# CH32F203K8T6-R0.net
KiCad netlist of a schematic drawn in Altium Designer
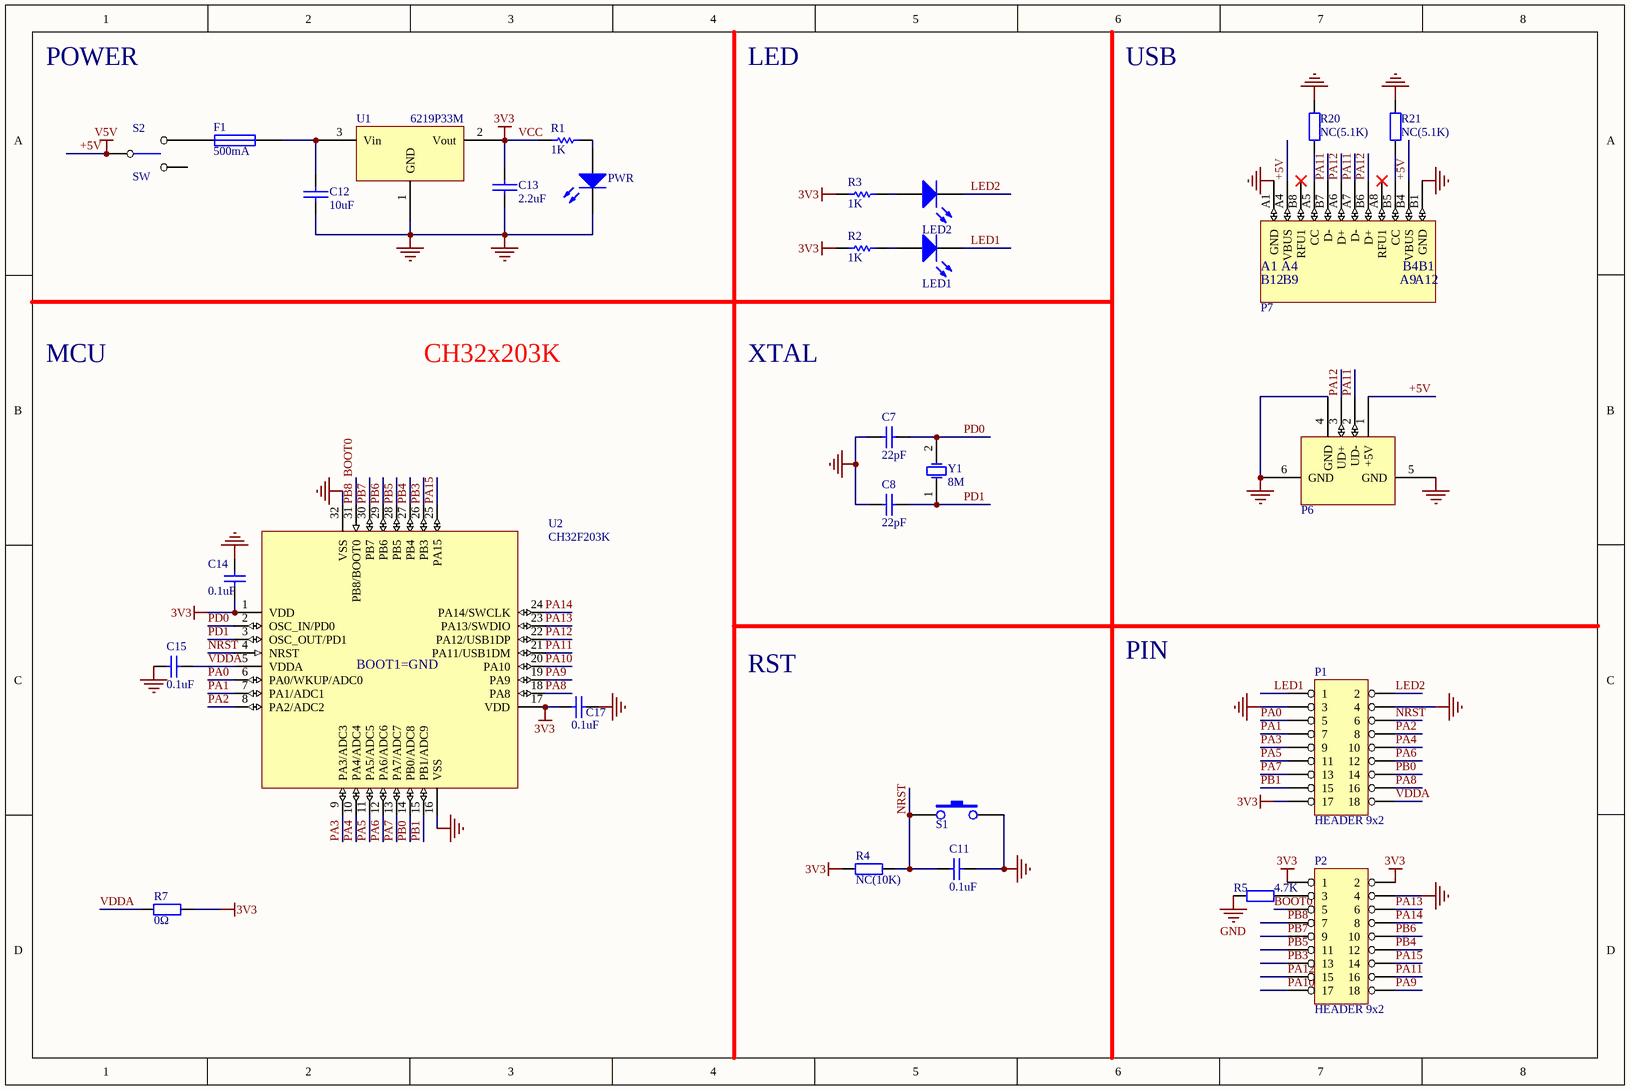
[diagram p0: CH32F203K8T6-R0.SchDoc]

(export (version "E")
  (design (tool "Eeschema 10.0.6"))
  (components
    (comp (ref "C7")
      (value "22pF")
      (footprint "0603_C")
      (description "Capacitor")
      (fields (field (name "PUBLISHER") "Altium Limited"))
      (libsource (lib "*") (part "Cap"))
    )
    (comp (ref "C8")
      (value "22pF")
      (footprint "0603_C")
      (description "Capacitor")
      (fields (field (name "PUBLISHER") "Altium Limited"))
      (libsource (lib "*") (part "Cap"))
    )
    (comp (ref "C11")
      (value "0.1uF")
      (footprint "0603_C")
      (description "Capacitor")
      (fields (field (name "PUBLISHER") "Altium Limited"))
      (libsource (lib "*") (part "Cap"))
    )
    (comp (ref "C12")
      (value "10uF")
      (footprint "3216_C")
      (description "Capacitor")
      (libsource (lib "wch_sch_others") (part "CAP"))
    )
    (comp (ref "C13")
      (value "2.2uF")
      (footprint "0603_C")
      (description "Capacitor")
      (libsource (lib "wch_sch_others") (part "CAP"))
    )
    (comp (ref "C14")
      (value "0.1uF")
      (footprint "0603_C")
      (description "Capacitor")
      (fields (field (name "PUBLISHER") "Altium Limited"))
      (libsource (lib "*") (part "Cap"))
    )
    (comp (ref "C15")
      (value "0.1uF")
      (footprint "0603_C")
      (description "Capacitor")
      (fields (field (name "PUBLISHER") "Altium Limited"))
      (libsource (lib "*") (part "Cap"))
    )
    (comp (ref "C17")
      (value "0.1uF")
      (footprint "0603_C")
      (description "Capacitor")
      (fields (field (name "PUBLISHER") "Altium Limited"))
      (libsource (lib "*") (part "Cap"))
    )
    (comp (ref "F1")
      (value "500mA")
      (footprint "0603")
      (description "Fuse")
      (libsource (lib "*") (part "FUSE1"))
    )
    (comp (ref "LED1")
      (value "LED1   blue")
      (footprint "0603+")
      (description "Typical INFRARED GaAs LED")
      (fields (field (name "PUBLISHER") "Altium Limited"))
      (libsource (lib "*") (part "LED0"))
    )
    (comp (ref "LED2")
      (value "LED2  blue")
      (footprint "0603+")
      (description "Typical INFRARED GaAs LED")
      (fields (field (name "PUBLISHER") "Altium Limited"))
      (libsource (lib "*") (part "LED0"))
    )
    (comp (ref "P1")
      (value "HEADER 9x2")
      (footprint "MYPCB:IDC18-2.54MM")
      (description "Header, 9-Pin, Dual row")
      (libsource (lib "wch_sch_others") (part "HEADER 9x2"))
    )
    (comp (ref "P2")
      (value "HEADER 9x2")
      (footprint "MYPCB:IDC18-2.54MM")
      (description "Header, 9-Pin, Dual row")
      (libsource (lib "wch_sch_others") (part "HEADER 9x2"))
    )
    (comp (ref "P6")
      (value "USB_A")
      (footprint "USBAF")
      (description "USB Port")
      (libsource (lib "*") (part "USB"))
    )
    (comp (ref "P7")
      (value "TYPE-C")
      (footprint "TYPE-C-Receptacle-2.0")
      (libsource (lib "*") (part "TYPE-C1"))
    )
    (comp (ref "PWR")
      (value "POWER  red")
      (footprint "0603+")
      (description "Typical INFRARED GaAs LED")
      (fields (field (name "PUBLISHER") "Altium Limited"))
      (libsource (lib "*") (part "LED0"))
    )
    (comp (ref "R1")
      (value "1K")
      (footprint "0603")
      (description "Semiconductor Resistor")
      (fields (field (name "PUBLISHER") "Altium Limited"))
      (libsource (lib "*") (part "Res Semi"))
    )
    (comp (ref "R2")
      (value "1K")
      (footprint "0603")
      (description "Semiconductor Resistor")
      (fields (field (name "PUBLISHER") "Altium Limited"))
      (libsource (lib "*") (part "Res Semi"))
    )
    (comp (ref "R3")
      (value "1K")
      (footprint "0603")
      (description "Semiconductor Resistor")
      (fields (field (name "PUBLISHER") "Altium Limited"))
      (libsource (lib "*") (part "Res Semi"))
    )
    (comp (ref "R4")
      (value "NC(10K)")
      (footprint "0603")
      (description "Resistor")
      (fields (field (name "PUBLISHER") "Altium Limited"))
      (libsource (lib "*") (part "Res2"))
    )
    (comp (ref "R5")
      (value "4.7K")
      (footprint "0603")
      (description "Resistor")
      (fields (field (name "PUBLISHER") "Altium Limited"))
      (libsource (lib "") (part "Res2_1"))
    )
    (comp (ref "R7")
      (value "0Ω")
      (footprint "0603")
      (description "Resistor")
      (fields (field (name "PUBLISHER") "Altium Limited"))
      (libsource (lib "*") (part "Res2"))
    )
    (comp (ref "R20")
      (value "NC(5.1K)")
      (footprint "0603")
      (description "Resistor")
      (libsource (lib "Miscellaneous Devices") (part "Res2"))
    )
    (comp (ref "R21")
      (value "NC(5.1K)")
      (footprint "0603")
      (description "Resistor")
      (libsource (lib "Miscellaneous Devices") (part "Res2"))
    )
    (comp (ref "S1") (value "RST") (footprint "SMD_6.1x3.65x2.5mm-KEY") (libsource (lib "*") (part "KEY")))
    (comp (ref "S2") (value "SW") (footprint "KEY2") (libsource (lib "*") (part "SW")))
    (comp (ref "U1")
      (value "6219P33M")
      (footprint "SOT-23")
      (libsource (lib "wch_sch_others") (part "6219P33M"))
    )
    (comp (ref "U2")
      (value "CH32F203K")
      (footprint "LQFP32")
      (description "ARM M3 LMD-MCU, 144MHz, USB FS, CAN")
      (libsource (lib "CHXXX") (part "CH32F203K"))
    )
    (comp (ref "Y1")
      (value "8M")
      (footprint "XT_AT49")
      (description "Crystal Oscillator")
      (fields (field (name "PUBLISHER") "Altium Limited"))
      (libsource (lib "*") (part "XTAL"))
    )
  )
  (nets
    (net (code "2") (name "/BOOT0") (class "Default")
      (node (ref "P2") (pin "5") (pinfunction "5_5") (pintype "passive"))
      (node (ref "P2") (pin "7") (pinfunction "7_7") (pintype "passive"))
      (node (ref "U2") (pin "31") (pinfunction "PB8/BOOT0_31") (pintype "input"))
    )
    (net (code "3") (name "/LED1") (class "Default")
      (node (ref "LED1") (pin "2") (pinfunction "K_2") (pintype "passive"))
      (node (ref "P1") (pin "1") (pinfunction "1_1") (pintype "passive"))
    )
    (net (code "4") (name "/LED2") (class "Default")
      (node (ref "LED2") (pin "2") (pinfunction "K_2") (pintype "passive"))
      (node (ref "P1") (pin "2") (pinfunction "2_2") (pintype "passive"))
    )
    (net (code "5") (name "/NRST") (class "Default")
      (node (ref "C11") (pin "2") (pinfunction "2_2") (pintype "passive"))
      (node (ref "P1") (pin "6") (pinfunction "6_6") (pintype "passive"))
      (node (ref "R4") (pin "1") (pinfunction "1_1") (pintype "passive"))
      (node (ref "S1") (pin "1") (pinfunction "1_1") (pintype "passive"))
      (node (ref "U2") (pin "4") (pinfunction "NRST_4") (pintype "input"))
    )
    (net (code "6") (name "/PA0") (class "Default")
      (node (ref "P1") (pin "5") (pinfunction "5_5") (pintype "passive"))
      (node (ref "U2") (pin "6") (pinfunction "PA0/WKUP/ADC0_6") (pintype "bidirectional"))
    )
    (net (code "7") (name "/PA1") (class "Default")
      (node (ref "P1") (pin "7") (pinfunction "7_7") (pintype "passive"))
      (node (ref "U2") (pin "7") (pinfunction "PA1/ADC1_7") (pintype "bidirectional"))
    )
    (net (code "8") (name "/PA2") (class "Default")
      (node (ref "P1") (pin "8") (pinfunction "8_8") (pintype "passive"))
      (node (ref "U2") (pin "8") (pinfunction "PA2/ADC2_8") (pintype "bidirectional"))
    )
    (net (code "9") (name "/PA3") (class "Default")
      (node (ref "P1") (pin "9") (pinfunction "9_9") (pintype "passive"))
      (node (ref "U2") (pin "9") (pinfunction "PA3/ADC3_9") (pintype "bidirectional"))
    )
    (net (code "10") (name "/PA4") (class "Default")
      (node (ref "P1") (pin "10") (pinfunction "10_10") (pintype "passive"))
      (node (ref "U2") (pin "10") (pinfunction "PA4/ADC4_10") (pintype "bidirectional"))
    )
    (net (code "11") (name "/PA5") (class "Default")
      (node (ref "P1") (pin "11") (pinfunction "11_11") (pintype "passive"))
      (node (ref "U2") (pin "11") (pinfunction "PA5/ADC5_11") (pintype "bidirectional"))
    )
    (net (code "12") (name "/PA6") (class "Default")
      (node (ref "P1") (pin "12") (pinfunction "12_12") (pintype "passive"))
      (node (ref "U2") (pin "12") (pinfunction "PA6/ADC6_12") (pintype "bidirectional"))
    )
    (net (code "13") (name "/PA7") (class "Default")
      (node (ref "P1") (pin "13") (pinfunction "13_13") (pintype "passive"))
      (node (ref "U2") (pin "13") (pinfunction "PA7/ADC7_13") (pintype "bidirectional"))
    )
    (net (code "14") (name "/PA8") (class "Default")
      (node (ref "P1") (pin "16") (pinfunction "16_16") (pintype "passive"))
      (node (ref "U2") (pin "18") (pinfunction "PA8_18") (pintype "bidirectional"))
    )
    (net (code "15") (name "/PA9") (class "Default")
      (node (ref "P2") (pin "18") (pinfunction "18_18") (pintype "passive"))
      (node (ref "U2") (pin "19") (pinfunction "PA9_19") (pintype "bidirectional"))
    )
    (net (code "16") (name "/PA10") (class "Default")
      (node (ref "P2") (pin "17") (pinfunction "17_17") (pintype "passive"))
      (node (ref "U2") (pin "20") (pinfunction "PA10_20") (pintype "bidirectional"))
    )
    (net (code "17") (name "/PA11") (class "Default")
      (node (ref "P2") (pin "16") (pinfunction "16_16") (pintype "passive"))
      (node (ref "P6") (pin "2") (pinfunction "UD-_2") (pintype "bidirectional"))
      (node (ref "P7") (pin "A7") (pinfunction "D-_A7") (pintype "bidirectional"))
      (node (ref "P7") (pin "B7") (pinfunction "D-_B7") (pintype "bidirectional"))
      (node (ref "U2") (pin "21") (pinfunction "PA11/USB1DM_21") (pintype "bidirectional"))
    )
    (net (code "18") (name "/PA12") (class "Default")
      (node (ref "P2") (pin "15") (pinfunction "15_15") (pintype "passive"))
      (node (ref "P6") (pin "3") (pinfunction "UD+_3") (pintype "bidirectional"))
      (node (ref "P7") (pin "A6") (pinfunction "D+_A6") (pintype "bidirectional"))
      (node (ref "P7") (pin "B6") (pinfunction "D+_B6") (pintype "bidirectional"))
      (node (ref "U2") (pin "22") (pinfunction "PA12/USB1DP_22") (pintype "bidirectional"))
    )
    (net (code "19") (name "/PA13") (class "Default")
      (node (ref "P2") (pin "6") (pinfunction "6_6") (pintype "passive"))
      (node (ref "U2") (pin "23") (pinfunction "PA13/SWDIO_23") (pintype "bidirectional"))
    )
    (net (code "20") (name "/PA14") (class "Default")
      (node (ref "P2") (pin "8") (pinfunction "8_8") (pintype "passive"))
      (node (ref "U2") (pin "24") (pinfunction "PA14/SWCLK_24") (pintype "bidirectional"))
    )
    (net (code "21") (name "/PA15") (class "Default")
      (node (ref "P2") (pin "14") (pinfunction "14_14") (pintype "passive"))
      (node (ref "U2") (pin "25") (pinfunction "PA15_25") (pintype "bidirectional"))
    )
    (net (code "22") (name "/PB0") (class "Default")
      (node (ref "P1") (pin "14") (pinfunction "14_14") (pintype "passive"))
      (node (ref "U2") (pin "14") (pinfunction "PB0/ADC8_14") (pintype "bidirectional"))
    )
    (net (code "23") (name "/PB1") (class "Default")
      (node (ref "P1") (pin "15") (pinfunction "15_15") (pintype "passive"))
      (node (ref "U2") (pin "15") (pinfunction "PB1/ADC9_15") (pintype "bidirectional"))
    )
    (net (code "24") (name "/PB3") (class "Default")
      (node (ref "P2") (pin "13") (pinfunction "13_13") (pintype "passive"))
      (node (ref "U2") (pin "26") (pinfunction "PB3_26") (pintype "bidirectional"))
    )
    (net (code "25") (name "/PB4") (class "Default")
      (node (ref "P2") (pin "12") (pinfunction "12_12") (pintype "passive"))
      (node (ref "U2") (pin "27") (pinfunction "PB4_27") (pintype "bidirectional"))
    )
    (net (code "26") (name "/PB5") (class "Default")
      (node (ref "P2") (pin "11") (pinfunction "11_11") (pintype "passive"))
      (node (ref "U2") (pin "28") (pinfunction "PB5_28") (pintype "bidirectional"))
    )
    (net (code "27") (name "/PB6") (class "Default")
      (node (ref "P2") (pin "10") (pinfunction "10_10") (pintype "passive"))
      (node (ref "U2") (pin "29") (pinfunction "PB6_29") (pintype "bidirectional"))
    )
    (net (code "28") (name "/PB7") (class "Default")
      (node (ref "P2") (pin "9") (pinfunction "9_9") (pintype "passive"))
      (node (ref "U2") (pin "30") (pinfunction "PB7_30") (pintype "bidirectional"))
    )
    (net (code "29") (name "/PD0") (class "Default")
      (node (ref "C7") (pin "2") (pinfunction "2_2") (pintype "passive"))
      (node (ref "U2") (pin "2") (pinfunction "OSC_IN/PD0_2") (pintype "bidirectional"))
      (node (ref "Y1") (pin "2") (pinfunction "OSC2_2") (pintype "passive"))
    )
    (net (code "30") (name "/PD1") (class "Default")
      (node (ref "C8") (pin "2") (pinfunction "2_2") (pintype "passive"))
      (node (ref "U2") (pin "3") (pinfunction "OSC_OUT/PD1_3") (pintype "bidirectional"))
      (node (ref "Y1") (pin "1") (pinfunction "OSC1_1") (pintype "passive"))
    )
    (net (code "31") (name "/VDDA") (class "Default")
      (node (ref "C15") (pin "1") (pinfunction "1_1") (pintype "passive"))
      (node (ref "P1") (pin "18") (pinfunction "18_18") (pintype "passive"))
      (node (ref "R7") (pin "2") (pinfunction "2_2") (pintype "passive"))
      (node (ref "U2") (pin "5") (pinfunction "VDDA_5") (pintype "power_in"))
    )
    (net (code "32") (name "3V3") (class "Default")
      (node (ref "C13") (pin "2") (pinfunction "2_2") (pintype "passive"))
      (node (ref "C14") (pin "2") (pinfunction "2_2") (pintype "passive"))
      (node (ref "C17") (pin "1") (pinfunction "1_1") (pintype "passive"))
      (node (ref "P1") (pin "17") (pinfunction "17_17") (pintype "passive"))
      (node (ref "P2") (pin "1") (pinfunction "1_1") (pintype "passive"))
      (node (ref "P2") (pin "2") (pinfunction "2_2") (pintype "passive"))
      (node (ref "R1") (pin "2") (pinfunction "2_2") (pintype "passive"))
      (node (ref "R2") (pin "1") (pinfunction "1_1") (pintype "passive"))
      (node (ref "R3") (pin "1") (pinfunction "1_1") (pintype "passive"))
      (node (ref "R4") (pin "2") (pinfunction "2_2") (pintype "passive"))
      (node (ref "R7") (pin "1") (pinfunction "1_1") (pintype "passive"))
      (node (ref "U1") (pin "2") (pinfunction "Vout_2") (pintype "passive"))
      (node (ref "U2") (pin "1") (pinfunction "VDD_1") (pintype "power_in"))
      (node (ref "U2") (pin "17") (pinfunction "VDD_17") (pintype "power_in"))
    )
    (net (code "33") (name "GND") (class "Default")
      (node (ref "C11") (pin "1") (pinfunction "1_1") (pintype "passive"))
      (node (ref "C12") (pin "2") (pinfunction "2_2") (pintype "passive"))
      (node (ref "C13") (pin "1") (pinfunction "1_1") (pintype "passive"))
      (node (ref "C14") (pin "1") (pinfunction "1_1") (pintype "passive"))
      (node (ref "C15") (pin "2") (pinfunction "2_2") (pintype "passive"))
      (node (ref "C17") (pin "2") (pinfunction "2_2") (pintype "passive"))
      (node (ref "C7") (pin "1") (pinfunction "1_1") (pintype "passive"))
      (node (ref "C8") (pin "1") (pinfunction "1_1") (pintype "passive"))
      (node (ref "P1") (pin "3") (pinfunction "3_3") (pintype "passive"))
      (node (ref "P1") (pin "4") (pinfunction "4_4") (pintype "passive"))
      (node (ref "P2") (pin "4") (pinfunction "4_4") (pintype "passive"))
      (node (ref "P6") (pin "4") (pinfunction "GND_4") (pintype "power_in"))
      (node (ref "P6") (pin "5") (pinfunction "GND_5") (pintype "power_in"))
      (node (ref "P6") (pin "6") (pinfunction "GND_6") (pintype "power_in"))
      (node (ref "P7") (pin "A1") (pinfunction "GND_A1") (pintype "bidirectional"))
      (node (ref "P7") (pin "B1") (pinfunction "GND_B1") (pintype "bidirectional"))
      (node (ref "PWR") (pin "2") (pinfunction "K_2") (pintype "passive"))
      (node (ref "R20") (pin "2") (pinfunction "2_2") (pintype "passive"))
      (node (ref "R21") (pin "2") (pinfunction "2_2") (pintype "passive"))
      (node (ref "R5") (pin "1") (pinfunction "1_1") (pintype "passive"))
      (node (ref "S1") (pin "2") (pinfunction "2_2") (pintype "passive"))
      (node (ref "U1") (pin "1") (pinfunction "GND_1") (pintype "passive"))
      (node (ref "U2") (pin "16") (pinfunction "VSS_16") (pintype "power_in"))
      (node (ref "U2") (pin "32") (pinfunction "VSS_32") (pintype "power_in"))
    )
    (net (code "34") (name "Net-(F1-Pad1)") (class "Default")
      (node (ref "F1") (pin "1") (pinfunction "1_1") (pintype "passive"))
      (node (ref "S2") (pin "3") (pinfunction "3_3") (pintype "passive"))
    )
    (net (code "35") (name "Net-(LED1-A)") (class "Default")
      (node (ref "LED1") (pin "1") (pinfunction "A_1") (pintype "passive"))
      (node (ref "R2") (pin "2") (pinfunction "2_2") (pintype "passive"))
    )
    (net (code "36") (name "Net-(LED2-A)") (class "Default")
      (node (ref "LED2") (pin "1") (pinfunction "A_1") (pintype "passive"))
      (node (ref "R3") (pin "2") (pinfunction "2_2") (pintype "passive"))
    )
    (net (code "37") (name "Net-(P2-Pad3)") (class "Default")
      (node (ref "P2") (pin "3") (pinfunction "3_3") (pintype "passive"))
      (node (ref "R5") (pin "2") (pinfunction "2_2") (pintype "passive"))
    )
    (net (code "38") (name "Net-(P7-CC-PadA5)") (class "Default")
      (node (ref "P7") (pin "A5") (pinfunction "CC_A5") (pintype "bidirectional"))
      (node (ref "R20") (pin "1") (pinfunction "1_1") (pintype "passive"))
    )
    (net (code "39") (name "Net-(P7-CC-PadB5)") (class "Default")
      (node (ref "P7") (pin "B5") (pinfunction "CC_B5") (pintype "bidirectional"))
      (node (ref "R21") (pin "1") (pinfunction "1_1") (pintype "passive"))
    )
    (net (code "40") (name "Net-(PWR-A)") (class "Default")
      (node (ref "PWR") (pin "1") (pinfunction "A_1") (pintype "passive"))
      (node (ref "R1") (pin "1") (pinfunction "1_1") (pintype "passive"))
    )
    (net (code "41") (name "Net-(U1-Vin)") (class "Default")
      (node (ref "C12") (pin "1") (pinfunction "1_1") (pintype "passive"))
      (node (ref "F1") (pin "2") (pinfunction "2_2") (pintype "passive"))
      (node (ref "U1") (pin "3") (pinfunction "Vin_3") (pintype "passive"))
    )
    (net (code "42") (name "V5V") (class "Default")
      (node (ref "P6") (pin "1") (pinfunction "+5V_1") (pintype "power_in"))
      (node (ref "P7") (pin "A4") (pinfunction "VBUS_A4") (pintype "bidirectional"))
      (node (ref "P7") (pin "B4") (pinfunction "VBUS_B4") (pintype "bidirectional"))
      (node (ref "S2") (pin "1") (pinfunction "1_1") (pintype "passive"))
    )
    (net (code "43") (name "unconnected-(P7-RFU1-PadA8)") (class "Default")
      (node (ref "P7") (pin "A8") (pinfunction "RFU1_A8") (pintype "bidirectional+no_connect"))
    )
    (net (code "44") (name "unconnected-(P7-RFU1-PadB8)") (class "Default")
      (node (ref "P7") (pin "B8") (pinfunction "RFU1_B8") (pintype "bidirectional+no_connect"))
    )
    (net (code "45") (name "unconnected-(S2-Pad2)") (class "Default")
      (node (ref "S2") (pin "2") (pinfunction "2_2") (pintype "passive"))
    )
  )
)
